# STM32H743IIT6.net
KiCad netlist of a schematic drawn in Altium Designer
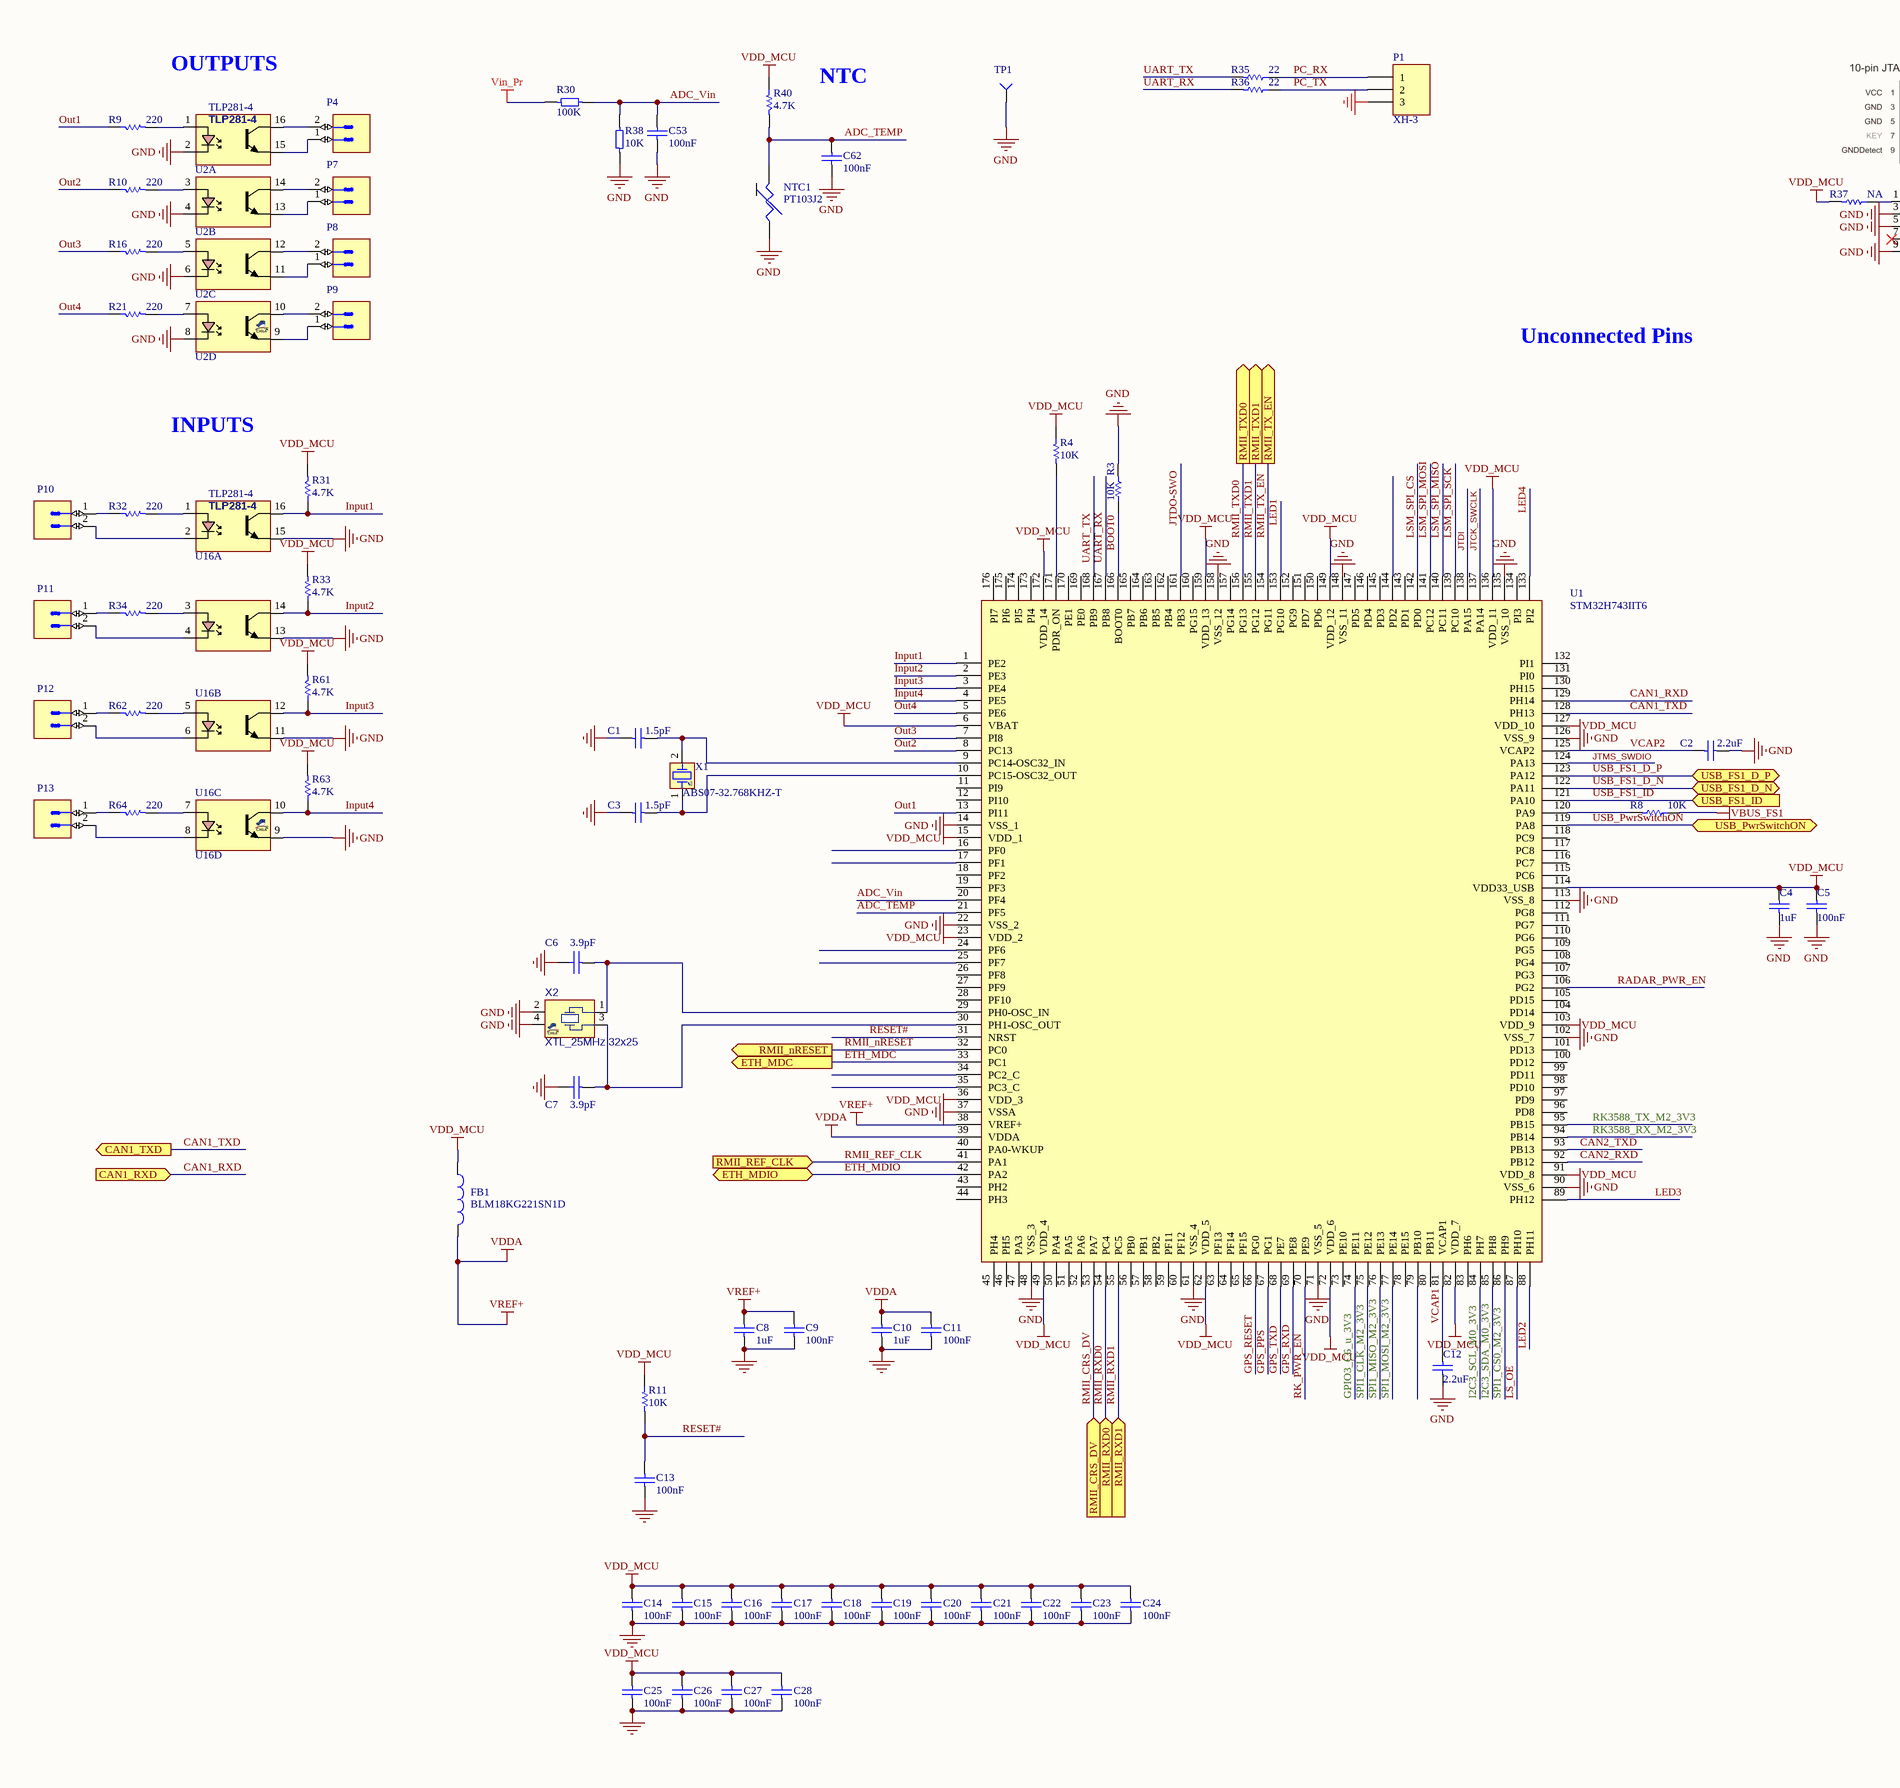
[diagram p0: STM32H743IIT6.SchDoc, left]
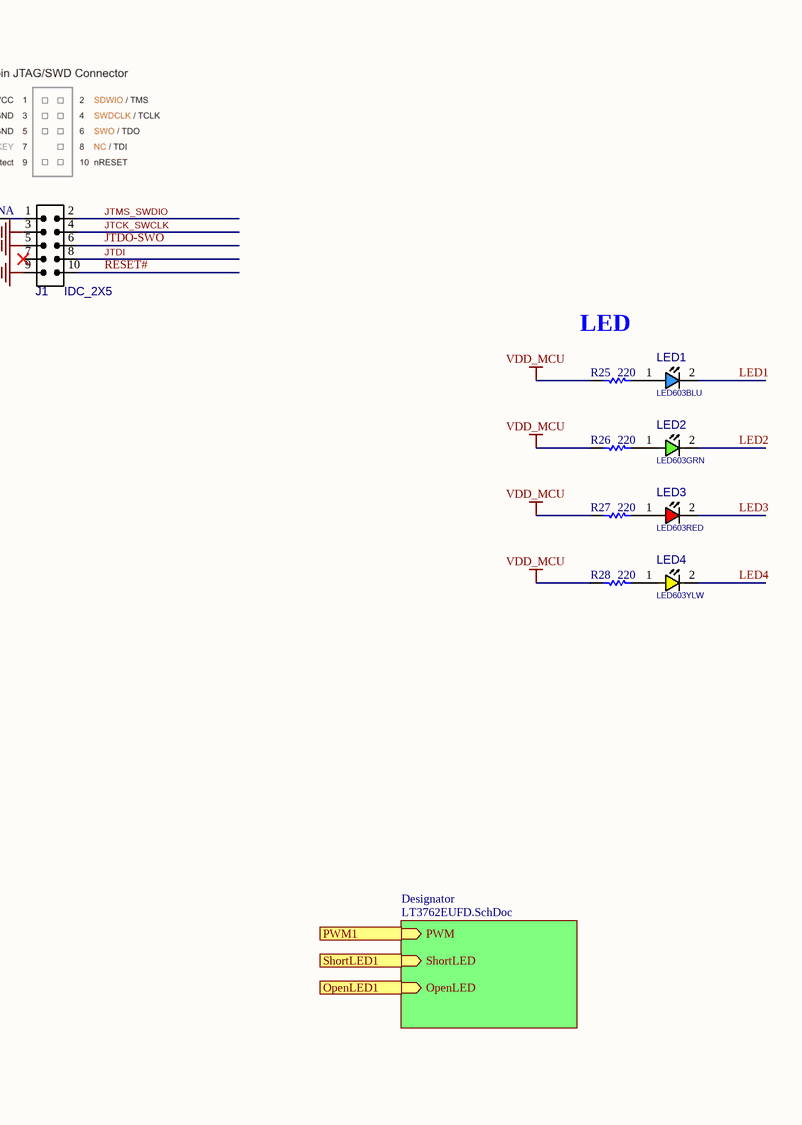
[diagram p1: STM32H743IIT6.SchDoc, right]

(export (version "E")
  (design (tool "Eeschema 10.0.6"))
  (components
    (comp (ref "C1") (value "1.5pF") (footprint "C0603") (libsource (lib "MCD_TOOLS") (part "Capacitor_ST")))
    (comp (ref "C2")
      (value "2.2uF")
      (footprint "C0603")
      (fields (field (name "PUBLISHER") "Altium Limited"))
      (libsource (lib "Miscellaneous Devices") (part "Cap"))
    )
    (comp (ref "C3") (value "1.5pF") (footprint "C0603") (libsource (lib "MCD_TOOLS") (part "Capacitor_ST")))
    (comp (ref "C4")
      (value "1uF")
      (footprint "C0603")
      (fields (field (name "PUBLISHER") "Altium Limited"))
      (libsource (lib "Miscellaneous Devices") (part "Cap"))
    )
    (comp (ref "C5")
      (value "100nF")
      (footprint "C0603")
      (fields (field (name "PUBLISHER") "Altium Limited"))
      (libsource (lib "Miscellaneous Devices") (part "Cap"))
    )
    (comp (ref "C6") (value "3.9pF") (footprint "C0603") (libsource (lib "*") (part "CAP")))
    (comp (ref "C7") (value "3.9pF") (footprint "C0603") (libsource (lib "*") (part "CAP")))
    (comp (ref "C8")
      (value "1uF")
      (footprint "C0603")
      (fields (field (name "PUBLISHER") "Altium Limited"))
      (libsource (lib "Miscellaneous Devices") (part "Cap"))
    )
    (comp (ref "C9")
      (value "100nF")
      (footprint "C0603")
      (fields (field (name "PUBLISHER") "Altium Limited"))
      (libsource (lib "Miscellaneous Devices") (part "Cap"))
    )
    (comp (ref "C10")
      (value "1uF")
      (footprint "C0603")
      (fields (field (name "PUBLISHER") "Altium Limited"))
      (libsource (lib "Miscellaneous Devices") (part "Cap"))
    )
    (comp (ref "C11")
      (value "100nF")
      (footprint "C0603")
      (fields (field (name "PUBLISHER") "Altium Limited"))
      (libsource (lib "Miscellaneous Devices") (part "Cap"))
    )
    (comp (ref "C12")
      (value "2.2uF")
      (footprint "C0603")
      (fields (field (name "PUBLISHER") "Altium Limited"))
      (libsource (lib "Miscellaneous Devices") (part "Cap"))
    )
    (comp (ref "C13")
      (value "100nF")
      (footprint "C0603")
      (fields (field (name "PUBLISHER") "Altium Limited"))
      (libsource (lib "Miscellaneous Devices") (part "CAP"))
    )
    (comp (ref "C14")
      (value "100nF")
      (footprint "C0603")
      (fields (field (name "PUBLISHER") "Altium Limited"))
      (libsource (lib "Miscellaneous Devices") (part "CAP"))
    )
    (comp (ref "C15")
      (value "100nF")
      (footprint "C0603")
      (fields (field (name "PUBLISHER") "Altium Limited"))
      (libsource (lib "Miscellaneous Devices") (part "CAP"))
    )
    (comp (ref "C16")
      (value "100nF")
      (footprint "C0603")
      (fields (field (name "PUBLISHER") "Altium Limited"))
      (libsource (lib "Miscellaneous Devices") (part "CAP"))
    )
    (comp (ref "C17")
      (value "100nF")
      (footprint "C0603")
      (fields (field (name "PUBLISHER") "Altium Limited"))
      (libsource (lib "Miscellaneous Devices") (part "CAP"))
    )
    (comp (ref "C18")
      (value "100nF")
      (footprint "C0603")
      (fields (field (name "PUBLISHER") "Altium Limited"))
      (libsource (lib "Miscellaneous Devices") (part "CAP"))
    )
    (comp (ref "C19")
      (value "100nF")
      (footprint "C0603")
      (fields (field (name "PUBLISHER") "Altium Limited"))
      (libsource (lib "Miscellaneous Devices") (part "CAP"))
    )
    (comp (ref "C20")
      (value "100nF")
      (footprint "C0603")
      (fields (field (name "PUBLISHER") "Altium Limited"))
      (libsource (lib "Miscellaneous Devices") (part "CAP"))
    )
    (comp (ref "C21")
      (value "100nF")
      (footprint "C0603")
      (fields (field (name "PUBLISHER") "Altium Limited"))
      (libsource (lib "Miscellaneous Devices") (part "CAP"))
    )
    (comp (ref "C22")
      (value "100nF")
      (footprint "C0603")
      (fields (field (name "PUBLISHER") "Altium Limited"))
      (libsource (lib "Miscellaneous Devices") (part "CAP"))
    )
    (comp (ref "C23")
      (value "100nF")
      (footprint "C0603")
      (fields (field (name "PUBLISHER") "Altium Limited"))
      (libsource (lib "Miscellaneous Devices") (part "CAP"))
    )
    (comp (ref "C24")
      (value "100nF")
      (footprint "C0603")
      (fields (field (name "PUBLISHER") "Altium Limited"))
      (libsource (lib "Miscellaneous Devices") (part "CAP"))
    )
    (comp (ref "C25")
      (value "100nF")
      (footprint "C0603")
      (fields (field (name "PUBLISHER") "Altium Limited"))
      (libsource (lib "Miscellaneous Devices") (part "CAP"))
    )
    (comp (ref "C26")
      (value "100nF")
      (footprint "C0603")
      (fields (field (name "PUBLISHER") "Altium Limited"))
      (libsource (lib "Miscellaneous Devices") (part "CAP"))
    )
    (comp (ref "C27")
      (value "100nF")
      (footprint "C0603")
      (fields (field (name "PUBLISHER") "Altium Limited"))
      (libsource (lib "Miscellaneous Devices") (part "CAP"))
    )
    (comp (ref "C28")
      (value "100nF")
      (footprint "C0603")
      (fields (field (name "PUBLISHER") "Altium Limited"))
      (libsource (lib "Miscellaneous Devices") (part "CAP"))
    )
    (comp (ref "C53")
      (value "100nF")
      (footprint "C0603")
      (fields (field (name "PUBLISHER") "Altium Limited"))
      (libsource (lib "Miscellaneous Devices") (part "CAP"))
    )
    (comp (ref "C62")
      (value "100nF")
      (footprint "C0603")
      (fields (field (name "PUBLISHER") "Altium Limited"))
      (libsource (lib "Miscellaneous Devices") (part "CAP"))
    )
    (comp (ref "FB1")
      (value "BLM18KG221SN1D")
      (footprint "L0603E")
      (description "Ferrite Bead")
      (fields (field (name "PUBLISHER") "Altium Limited"))
      (libsource (lib "Miscellaneous Devices") (part "Inductor"))
    )
    (comp (ref "J1")
      (value "IDC_2X5")
      (footprint "IDC_2X5")
      (description "CONN, IDC, Male, pitch: 2.54mm, 10POS")
      (libsource (lib "conn_header_idc") (part "IDC_2X5"))
    )
    (comp (ref "LED1")
      (value "LED603BLU")
      (footprint "LED0603BLU")
      (description "LED, SMD, 0603, BLUE")
      (fields (field (name "MANF") "MANF") (field (name "MANF_P#") "MANF_PART#"))
      (libsource (lib "led(diode)") (part "LED_SMD_0603_BLU"))
    )
    (comp (ref "LED2")
      (value "LED603GRN")
      (footprint "LED0603GRN")
      (description "LED, SMD, 0603, GREEN")
      (fields (field (name "MANF") "Kingbright") (field (name "MANF_P#") "APT1608SGC"))
      (libsource (lib "led(diode)") (part "LED_SMD_0603_GRN"))
    )
    (comp (ref "LED3")
      (value "LED603RED")
      (footprint "LED0603RED")
      (description "LED, SMD, 0603, RED")
      (fields (field (name "MANF") "MANF") (field (name "MANF_P#") "MANF_PART#"))
      (libsource (lib "led(diode)") (part "LED_SMD_0603_RED"))
    )
    (comp (ref "LED4")
      (value "LED603YLW")
      (footprint "LED0603YLW")
      (description "LED, SMD, 0603, YELLOW")
      (fields (field (name "MANF") "MANF") (field (name "MANF_P#") "MANF_PART#"))
      (libsource (lib "led(diode)") (part "LED_SMD_0603_YLW"))
    )
    (comp (ref "NTC1")
      (value "PT103J2")
      (footprint "HDR1X2")
      (description "THERMISTOR 10K OHM +/-0.20 C")
      (libsource (lib "J ABDAR-Altium-LibV1") (part "NTC power"))
    )
    (comp (ref "P1")
      (value "XH-3")
      (footprint "xh-3")
      (description "Header, 3-Pin")
      (fields (field (name "PUBLISHER") "Altium Limited"))
      (libsource (lib "Miscellaneous Connectors") (part "Header 3"))
    )
    (comp (ref "P4")
      (value "JST PH 2mm 2P RIGHT")
      (footprint "JST B2B-PH-K")
      (description "JST PH 2P RIGHT")
      (fields
        (field (name "PART NUMBER") "PHOENIX_1803426")
        (field (name "MANUFACTURER") "PHOENIX CONTACT")
        (field (name "AUTHOR") "CERN DEM JLC")
      )
      (libsource (lib "") (part "Connector 2 Male_1"))
    )
    (comp (ref "P7")
      (value "JST PH 2mm 2P RIGHT")
      (footprint "JST B2B-PH-K")
      (description "JST PH 2P RIGHT")
      (fields
        (field (name "PART NUMBER") "PHOENIX_1803426")
        (field (name "MANUFACTURER") "PHOENIX CONTACT")
        (field (name "AUTHOR") "CERN DEM JLC")
      )
      (libsource (lib "") (part "Connector 2 Male_1"))
    )
    (comp (ref "P8")
      (value "JST PH 2mm 2P RIGHT")
      (footprint "JST B2B-PH-K")
      (description "JST PH 2P RIGHT")
      (fields
        (field (name "PART NUMBER") "PHOENIX_1803426")
        (field (name "MANUFACTURER") "PHOENIX CONTACT")
        (field (name "AUTHOR") "CERN DEM JLC")
      )
      (libsource (lib "") (part "Connector 2 Male_1"))
    )
    (comp (ref "P9")
      (value "JST PH 2mm 2P RIGHT")
      (footprint "JST B2B-PH-K")
      (description "JST PH 2P RIGHT")
      (fields
        (field (name "PART NUMBER") "PHOENIX_1803426")
        (field (name "MANUFACTURER") "PHOENIX CONTACT")
        (field (name "AUTHOR") "CERN DEM JLC")
      )
      (libsource (lib "") (part "Connector 2 Male_1"))
    )
    (comp (ref "P10")
      (value "JST PH 2mm 2P RIGHT")
      (footprint "JST B2B-PH-K")
      (description "JST PH 2P RIGHT")
      (fields
        (field (name "PART NUMBER") "PHOENIX_1803426")
        (field (name "MANUFACTURER") "PHOENIX CONTACT")
        (field (name "AUTHOR") "CERN DEM JLC")
      )
      (libsource (lib "Connectors") (part "Connector 2 Male"))
    )
    (comp (ref "P11")
      (value "JST PH 2mm 2P RIGHT")
      (footprint "JST B2B-PH-K")
      (description "JST PH 2P RIGHT")
      (fields
        (field (name "PART NUMBER") "PHOENIX_1803426")
        (field (name "MANUFACTURER") "PHOENIX CONTACT")
        (field (name "AUTHOR") "CERN DEM JLC")
      )
      (libsource (lib "Connectors") (part "Connector 2 Male"))
    )
    (comp (ref "P12")
      (value "JST PH 2mm 2P RIGHT")
      (footprint "JST B2B-PH-K")
      (description "JST PH 2P RIGHT")
      (fields
        (field (name "PART NUMBER") "PHOENIX_1803426")
        (field (name "MANUFACTURER") "PHOENIX CONTACT")
        (field (name "AUTHOR") "CERN DEM JLC")
      )
      (libsource (lib "Connectors") (part "Connector 2 Male"))
    )
    (comp (ref "P13")
      (value "JST PH 2mm 2P RIGHT")
      (footprint "JST B2B-PH-K")
      (description "JST PH 2P RIGHT")
      (fields
        (field (name "PART NUMBER") "PHOENIX_1803426")
        (field (name "MANUFACTURER") "PHOENIX CONTACT")
        (field (name "AUTHOR") "CERN DEM JLC")
      )
      (libsource (lib "Connectors") (part "Connector 2 Male"))
    )
    (comp (ref "R3")
      (value "10K")
      (footprint "R0603")
      (fields (field (name "PUBLISHER") "Altium Limited"))
      (libsource (lib "Miscellaneous Devices") (part "res1"))
    )
    (comp (ref "R4")
      (value "10K")
      (footprint "R0603")
      (fields (field (name "PUBLISHER") "Altium Limited"))
      (libsource (lib "Miscellaneous Devices") (part "Res1"))
    )
    (comp (ref "R8")
      (value "10K")
      (footprint "R0603")
      (fields (field (name "PUBLISHER") "Altium Limited"))
      (libsource (lib "Miscellaneous Devices") (part "Res1"))
    )
    (comp (ref "R9")
      (value "220")
      (footprint "R0603")
      (fields (field (name "PUBLISHER") "Altium Limited"))
      (libsource (lib "Miscellaneous Devices") (part "Res1"))
    )
    (comp (ref "R10")
      (value "220")
      (footprint "R0603")
      (fields (field (name "PUBLISHER") "Altium Limited"))
      (libsource (lib "Miscellaneous Devices") (part "Res1"))
    )
    (comp (ref "R11")
      (value "10K")
      (footprint "R0603")
      (fields (field (name "PUBLISHER") "Altium Limited"))
      (libsource (lib "Miscellaneous Devices") (part "Res1"))
    )
    (comp (ref "R16")
      (value "220")
      (footprint "R0603")
      (fields (field (name "PUBLISHER") "Altium Limited"))
      (libsource (lib "Miscellaneous Devices") (part "Res1"))
    )
    (comp (ref "R21")
      (value "220")
      (footprint "R0603")
      (fields (field (name "PUBLISHER") "Altium Limited"))
      (libsource (lib "Miscellaneous Devices") (part "Res1"))
    )
    (comp (ref "R25")
      (value "220")
      (footprint "R0603")
      (fields (field (name "PUBLISHER") "Altium Limited"))
      (libsource (lib "Miscellaneous Devices") (part "Res1"))
    )
    (comp (ref "R26")
      (value "220")
      (footprint "R0603")
      (fields (field (name "PUBLISHER") "Altium Limited"))
      (libsource (lib "Miscellaneous Devices") (part "Res1"))
    )
    (comp (ref "R27")
      (value "220")
      (footprint "R0603")
      (fields (field (name "PUBLISHER") "Altium Limited"))
      (libsource (lib "Miscellaneous Devices") (part "Res1"))
    )
    (comp (ref "R28")
      (value "220")
      (footprint "R0603")
      (fields (field (name "PUBLISHER") "Altium Limited"))
      (libsource (lib "Miscellaneous Devices") (part "Res1"))
    )
    (comp (ref "R30")
      (value "100K")
      (footprint "R0603")
      (libsource (lib "Rahimi librery") (part "Resistor SMD"))
    )
    (comp (ref "R31")
      (value "4.7K")
      (footprint "R0603")
      (fields (field (name "PUBLISHER") "Altium Limited"))
      (libsource (lib "Miscellaneous Devices") (part "Res1"))
    )
    (comp (ref "R32")
      (value "220")
      (footprint "R0603")
      (fields (field (name "PUBLISHER") "Altium Limited"))
      (libsource (lib "Miscellaneous Devices") (part "Res1"))
    )
    (comp (ref "R33")
      (value "4.7K")
      (footprint "R0603")
      (fields (field (name "PUBLISHER") "Altium Limited"))
      (libsource (lib "Miscellaneous Devices") (part "Res1"))
    )
    (comp (ref "R34")
      (value "220")
      (footprint "R0603")
      (fields (field (name "PUBLISHER") "Altium Limited"))
      (libsource (lib "Miscellaneous Devices") (part "Res1"))
    )
    (comp (ref "R35")
      (value "22")
      (footprint "R0603")
      (fields (field (name "PUBLISHER") "Altium Limited"))
      (libsource (lib "Miscellaneous Devices") (part "res1"))
    )
    (comp (ref "R36")
      (value "22")
      (footprint "R0603")
      (fields (field (name "PUBLISHER") "Altium Limited"))
      (libsource (lib "Miscellaneous Devices") (part "res1"))
    )
    (comp (ref "R37")
      (value "NA")
      (footprint "R0603")
      (fields (field (name "PUBLISHER") "Altium Limited"))
      (libsource (lib "Miscellaneous Devices") (part "Res1"))
    )
    (comp (ref "R38")
      (value "10K")
      (footprint "R0603")
      (libsource (lib "Rahimi librery") (part "Resistor SMD"))
    )
    (comp (ref "R40")
      (value "4.7K")
      (footprint "R0603")
      (fields (field (name "PUBLISHER") "Altium Limited"))
      (libsource (lib "Miscellaneous Devices") (part "Res1"))
    )
    (comp (ref "R61")
      (value "4.7K")
      (footprint "R0603")
      (fields (field (name "PUBLISHER") "Altium Limited"))
      (libsource (lib "Miscellaneous Devices") (part "Res1"))
    )
    (comp (ref "R62")
      (value "220")
      (footprint "R0603")
      (fields (field (name "PUBLISHER") "Altium Limited"))
      (libsource (lib "Miscellaneous Devices") (part "Res1"))
    )
    (comp (ref "R63")
      (value "4.7K")
      (footprint "R0603")
      (fields (field (name "PUBLISHER") "Altium Limited"))
      (libsource (lib "Miscellaneous Devices") (part "Res1"))
    )
    (comp (ref "R64")
      (value "220")
      (footprint "R0603")
      (fields (field (name "PUBLISHER") "Altium Limited"))
      (libsource (lib "Miscellaneous Devices") (part "Res1"))
    )
    (comp (ref "TP1")
      (value "TEST POINT")
      (footprint "TEST_POINT")
      (libsource (lib "Tracker_MAIN_V1.01") (part "TEST POINT"))
    )
    (comp (ref "U1")
      (value "STM32H743IIT6")
      (footprint "QFP50P2600X2600X160-176N")
      (description "Integrated Circuit")
      (fields (field (name "MOUSER PART NUMBER") "511-STM32H743IIT6"))
      (libsource (lib "*") (part "STM32H743IIT6"))
    )
    (comp (ref "U2")
      (value "TLP281-4")
      (footprint "SO_16")
      (description "OPTOCOUPLER, TRANSISTOR, QUAD")
      (fields (field (name "MANF_P#") "TLP281-4A"))
      (libsource (lib "optocoupler") (part "OPTC_TR16P_TLP281-4_SMD"))
    )
    (comp (ref "U16")
      (value "TLP281-4")
      (footprint "SO_16")
      (description "OPTOCOUPLER, TRANSISTOR, QUAD")
      (fields (field (name "MANF_P#") "TLP281-4A"))
      (libsource (lib "optocoupler") (part "OPTC_TR16P_TLP281-4_SMD"))
    )
    (comp (ref "X1")
      (value "ABS07-32.768KHZ-T")
      (footprint "XTL_2_3215")
      (description "Crystal, 32.768KHz, 3pF, 20PPM")
      (fields (field (name "MANF") "ABRACON") (field (name "MANF_P#") "ABS07W-32.768kHz-D-2-T"))
      (libsource (lib "crystal") (part "XTL_2_32.768_3215A"))
    )
    (comp (ref "X2")
      (value "XTL_25MHz 32x25")
      (footprint "XTL_4_3225")
      (description "CRYSTAL 25.00 MHZ 18pF, 10PPM")
      (fields (field (name "MANF") "EPSON") (field (name "MANF_P#") "TSX-3225 25.0000MF10P-C3"))
      (libsource (lib "crystal") (part "XTL_4_25MHz_3225"))
    )
  )
  (nets
    (net (code "1") (name "/ADC_TEMP") (class "Default")
      (node (ref "C62") (pin "2") (pinfunction "2_2") (pintype "passive"))
      (node (ref "NTC1") (pin "2") (pintype "passive"))
      (node (ref "R40") (pin "2") (pinfunction "2_2") (pintype "passive"))
      (node (ref "U1") (pin "21") (pinfunction "PF5_21") (pintype "passive"))
    )
    (net (code "2") (name "/ADC_Vin") (class "Default")
      (node (ref "C53") (pin "2") (pinfunction "2_2") (pintype "passive"))
      (node (ref "R30") (pin "2") (pintype "passive"))
      (node (ref "R38") (pin "2") (pintype "passive"))
      (node (ref "U1") (pin "20") (pinfunction "PF4_20") (pintype "passive"))
    )
    (net (code "3") (name "/BOOT0") (class "Default")
      (node (ref "R3") (pin "1") (pinfunction "1_1") (pintype "passive"))
      (node (ref "U1") (pin "166") (pinfunction "BOOT0_166") (pintype "passive"))
    )
    (net (code "4") (name "/CAN1_RXD") (class "Default")
      (node (ref "U1") (pin "129") (pinfunction "PH14_129") (pintype "passive"))
    )
    (net (code "5") (name "/CAN1_TXD") (class "Default")
      (node (ref "U1") (pin "128") (pinfunction "PH13_128") (pintype "passive"))
    )
    (net (code "6") (name "/CAN2_RXD") (class "Default")
      (node (ref "U1") (pin "92") (pinfunction "PB12_92") (pintype "passive"))
    )
    (net (code "7") (name "/CAN2_TXD") (class "Default")
      (node (ref "U1") (pin "93") (pinfunction "PB13_93") (pintype "passive"))
    )
    (net (code "8") (name "/ETH_MDC") (class "Default")
      (node (ref "U1") (pin "33") (pinfunction "PC1_33") (pintype "passive"))
    )
    (net (code "9") (name "/ETH_MDIO") (class "Default")
      (node (ref "U1") (pin "42") (pinfunction "PA2_42") (pintype "passive"))
    )
    (net (code "10") (name "/GPIO3_C6_u_3V3") (class "Default")
      (node (ref "U1") (pin "74") (pinfunction "PE11_74") (pintype "passive"))
    )
    (net (code "11") (name "/GPS_PPS") (class "Default")
      (node (ref "U1") (pin "67") (pinfunction "PG1_67") (pintype "passive"))
    )
    (net (code "12") (name "/GPS_RESET") (class "Default")
      (node (ref "U1") (pin "66") (pinfunction "PG0_66") (pintype "passive"))
    )
    (net (code "13") (name "/GPS_RXD") (class "Default")
      (node (ref "U1") (pin "69") (pinfunction "PE8_69") (pintype "passive"))
    )
    (net (code "14") (name "/GPS_TXD") (class "Default")
      (node (ref "U1") (pin "68") (pinfunction "PE7_68") (pintype "passive"))
    )
    (net (code "15") (name "/I2C3_SCL_M0_3V3") (class "Default")
      (node (ref "U1") (pin "84") (pinfunction "PH7_84") (pintype "passive"))
    )
    (net (code "16") (name "/I2C3_SDA_M0_3V3") (class "Default")
      (node (ref "U1") (pin "85") (pinfunction "PH8_85") (pintype "passive"))
    )
    (net (code "17") (name "/Input1") (class "Default")
      (node (ref "R31") (pin "1") (pinfunction "1_1") (pintype "passive"))
      (node (ref "U1") (pin "1") (pinfunction "PE2_1") (pintype "passive"))
      (node (ref "U16") (pin "16") (pinfunction "16_16") (pintype "power_in"))
    )
    (net (code "18") (name "/Input2") (class "Default")
      (node (ref "R33") (pin "1") (pinfunction "1_1") (pintype "passive"))
      (node (ref "U1") (pin "2") (pinfunction "PE3_2") (pintype "passive"))
      (node (ref "U16") (pin "14") (pinfunction "14_14") (pintype "power_in"))
    )
    (net (code "19") (name "/Input3") (class "Default")
      (node (ref "R61") (pin "1") (pinfunction "1_1") (pintype "passive"))
      (node (ref "U1") (pin "3") (pinfunction "PE4_3") (pintype "passive"))
      (node (ref "U16") (pin "12") (pinfunction "12_12") (pintype "power_in"))
    )
    (net (code "20") (name "/Input4") (class "Default")
      (node (ref "R63") (pin "1") (pinfunction "1_1") (pintype "passive"))
      (node (ref "U1") (pin "4") (pinfunction "PE5_4") (pintype "passive"))
      (node (ref "U16") (pin "10") (pinfunction "10_10") (pintype "power_in"))
    )
    (net (code "21") (name "/JTCK_SWCLK") (class "Default")
      (node (ref "J1") (pin "4") (pinfunction "4_4") (pintype "passive"))
      (node (ref "U1") (pin "137") (pinfunction "PA14_137") (pintype "passive"))
    )
    (net (code "22") (name "/JTDI") (class "Default")
      (node (ref "J1") (pin "8") (pinfunction "8_8") (pintype "passive"))
      (node (ref "U1") (pin "138") (pinfunction "PA15_138") (pintype "passive"))
    )
    (net (code "23") (name "/JTDO-SWO") (class "Default")
      (node (ref "J1") (pin "6") (pinfunction "6_6") (pintype "passive"))
      (node (ref "U1") (pin "161") (pinfunction "PB3_161") (pintype "passive"))
    )
    (net (code "24") (name "/JTMS_SWDIO") (class "Default")
      (node (ref "J1") (pin "2") (pinfunction "2_2") (pintype "passive"))
      (node (ref "U1") (pin "124") (pinfunction "PA13_124") (pintype "passive"))
    )
    (net (code "25") (name "/LED1") (class "Default")
      (node (ref "LED1") (pin "2") (pinfunction "CATHODE_2") (pintype "passive"))
      (node (ref "U1") (pin "153") (pinfunction "PG10_153") (pintype "passive"))
    )
    (net (code "26") (name "/LED2") (class "Default")
      (node (ref "LED2") (pin "2") (pinfunction "CATHODE_2") (pintype "passive"))
      (node (ref "U1") (pin "88") (pinfunction "PH11_88") (pintype "passive"))
    )
    (net (code "27") (name "/LED3") (class "Default")
      (node (ref "LED3") (pin "2") (pinfunction "CATHODE_2") (pintype "passive"))
      (node (ref "U1") (pin "89") (pinfunction "PH12_89") (pintype "passive"))
    )
    (net (code "28") (name "/LED4") (class "Default")
      (node (ref "LED4") (pin "2") (pinfunction "CATHODE_2") (pintype "passive"))
      (node (ref "U1") (pin "133") (pinfunction "PI2_133") (pintype "passive"))
    )
    (net (code "29") (name "/LSM_SPI_CS") (class "Default")
      (node (ref "U1") (pin "142") (pinfunction "PD0_142") (pintype "passive"))
    )
    (net (code "30") (name "/LSM_SPI_MISO") (class "Default")
      (node (ref "U1") (pin "140") (pinfunction "PC11_140") (pintype "passive"))
    )
    (net (code "31") (name "/LSM_SPI_MOSI") (class "Default")
      (node (ref "U1") (pin "141") (pinfunction "PC12_141") (pintype "passive"))
    )
    (net (code "32") (name "/LSM_SPI_SCK") (class "Default")
      (node (ref "U1") (pin "139") (pinfunction "PC10_139") (pintype "passive"))
    )
    (net (code "33") (name "/LS_OE") (class "Default")
      (node (ref "U1") (pin "87") (pinfunction "PH10_87") (pintype "passive"))
    )
    (net (code "35") (name "/Out1") (class "Default")
      (node (ref "R9") (pin "1") (pinfunction "1_1") (pintype "passive"))
      (node (ref "U1") (pin "13") (pinfunction "PI11_13") (pintype "passive"))
    )
    (net (code "36") (name "/Out2") (class "Default")
      (node (ref "R10") (pin "1") (pinfunction "1_1") (pintype "passive"))
      (node (ref "U1") (pin "8") (pinfunction "PC13_8") (pintype "passive"))
    )
    (net (code "37") (name "/Out3") (class "Default")
      (node (ref "R16") (pin "1") (pinfunction "1_1") (pintype "passive"))
      (node (ref "U1") (pin "7") (pinfunction "PI8_7") (pintype "passive"))
    )
    (net (code "38") (name "/Out4") (class "Default")
      (node (ref "R21") (pin "1") (pinfunction "1_1") (pintype "passive"))
      (node (ref "U1") (pin "5") (pinfunction "PE6_5") (pintype "passive"))
    )
    (net (code "39") (name "/PC_RX") (class "Default")
      (node (ref "P1") (pin "1") (pinfunction "1_1") (pintype "passive"))
      (node (ref "R35") (pin "1") (pinfunction "1_1") (pintype "passive"))
    )
    (net (code "40") (name "/PC_TX") (class "Default")
      (node (ref "P1") (pin "2") (pinfunction "2_2") (pintype "passive"))
      (node (ref "R36") (pin "1") (pinfunction "1_1") (pintype "passive"))
    )
    (net (code "42") (name "/RADAR_PWR_EN") (class "Default")
      (node (ref "U1") (pin "106") (pinfunction "PG2_106") (pintype "passive"))
    )
    (net (code "43") (name "/RESET#") (class "Default")
      (node (ref "C13") (pin "2") (pinfunction "2_2") (pintype "passive"))
      (node (ref "J1") (pin "10") (pinfunction "10_10") (pintype "passive"))
      (node (ref "R11") (pin "2") (pinfunction "2_2") (pintype "passive"))
      (node (ref "U1") (pin "31") (pinfunction "NRST_31") (pintype "passive"))
    )
    (net (code "44") (name "/RK3588_RX_M2_3V3") (class "Default")
      (node (ref "U1") (pin "94") (pinfunction "PB14_94") (pintype "passive"))
    )
    (net (code "45") (name "/RK3588_TX_M2_3V3") (class "Default")
      (node (ref "U1") (pin "95") (pinfunction "PB15_95") (pintype "passive"))
    )
    (net (code "46") (name "/RK_PWR_EN") (class "Default")
      (node (ref "U1") (pin "70") (pinfunction "PE9_70") (pintype "passive"))
    )
    (net (code "47") (name "/RMII_CRS_DV") (class "Default")
      (node (ref "U1") (pin "53") (pinfunction "PA7_53") (pintype "passive"))
    )
    (net (code "48") (name "/RMII_REF_CLK") (class "Default")
      (node (ref "U1") (pin "41") (pinfunction "PA1_41") (pintype "passive"))
    )
    (net (code "49") (name "/RMII_RXD0") (class "Default")
      (node (ref "U1") (pin "54") (pinfunction "PC4_54") (pintype "passive"))
    )
    (net (code "50") (name "/RMII_RXD1") (class "Default")
      (node (ref "U1") (pin "55") (pinfunction "PC5_55") (pintype "passive"))
    )
    (net (code "51") (name "/RMII_TXD0") (class "Default")
      (node (ref "U1") (pin "156") (pinfunction "PG13_156") (pintype "passive"))
    )
    (net (code "52") (name "/RMII_TXD1") (class "Default")
      (node (ref "U1") (pin "155") (pinfunction "PG12_155") (pintype "passive"))
    )
    (net (code "53") (name "/RMII_TX_EN") (class "Default")
      (node (ref "U1") (pin "154") (pinfunction "PG11_154") (pintype "passive"))
    )
    (net (code "54") (name "/RMII_nRESET") (class "Default")
      (node (ref "U1") (pin "32") (pinfunction "PC0_32") (pintype "passive"))
    )
    (net (code "55") (name "/SPI1_CLK_M2_3V3") (class "Default")
      (node (ref "U1") (pin "75") (pinfunction "PE12_75") (pintype "passive"))
    )
    (net (code "56") (name "/SPI1_CS0_M2_3V3") (class "Default")
      (node (ref "U1") (pin "86") (pinfunction "PH9_86") (pintype "passive"))
    )
    (net (code "57") (name "/SPI1_MISO_M2_3V3") (class "Default")
      (node (ref "U1") (pin "76") (pinfunction "PE13_76") (pintype "passive"))
    )
    (net (code "58") (name "/SPI1_MOSI_M2_3V3") (class "Default")
      (node (ref "U1") (pin "77") (pinfunction "PE14_77") (pintype "passive"))
    )
    (net (code "60") (name "/UART_RX") (class "Default")
      (node (ref "R36") (pin "2") (pinfunction "2_2") (pintype "passive"))
      (node (ref "U1") (pin "167") (pinfunction "PB8_167") (pintype "passive"))
    )
    (net (code "61") (name "/UART_TX") (class "Default")
      (node (ref "R35") (pin "2") (pinfunction "2_2") (pintype "passive"))
      (node (ref "U1") (pin "168") (pinfunction "PB9_168") (pintype "passive"))
    )
    (net (code "62") (name "/USB_FS1_D_N") (class "Default")
      (node (ref "U1") (pin "122") (pinfunction "PA11_122") (pintype "passive"))
    )
    (net (code "63") (name "/USB_FS1_D_P") (class "Default")
      (node (ref "U1") (pin "123") (pinfunction "PA12_123") (pintype "passive"))
    )
    (net (code "64") (name "/USB_FS1_ID") (class "Default")
      (node (ref "U1") (pin "121") (pinfunction "PA10_121") (pintype "passive"))
    )
    (net (code "65") (name "/USB_PwrSwitchON") (class "Default")
      (node (ref "U1") (pin "119") (pinfunction "PA8_119") (pintype "passive"))
    )
    (net (code "66") (name "/VCAP1") (class "Default")
      (node (ref "C12") (pin "2") (pinfunction "2_2") (pintype "passive"))
      (node (ref "U1") (pin "81") (pinfunction "VCAP1_81") (pintype "power_in"))
    )
    (net (code "67") (name "/VCAP2") (class "Default")
      (node (ref "C2") (pin "1") (pinfunction "1_1") (pintype "passive"))
      (node (ref "U1") (pin "125") (pinfunction "VCAP2_125") (pintype "power_in"))
    )
    (net (code "68") (name "GND") (class "Default")
      (node (ref "C1") (pin "2") (pinfunction "2_2") (pintype "passive"))
      (node (ref "C10") (pin "1") (pinfunction "1_1") (pintype "passive"))
      (node (ref "C11") (pin "1") (pinfunction "1_1") (pintype "passive"))
      (node (ref "C12") (pin "1") (pinfunction "1_1") (pintype "passive"))
      (node (ref "C13") (pin "1") (pinfunction "1_1") (pintype "passive"))
      (node (ref "C14") (pin "2") (pinfunction "2_2") (pintype "passive"))
      (node (ref "C15") (pin "2") (pinfunction "2_2") (pintype "passive"))
      (node (ref "C16") (pin "2") (pinfunction "2_2") (pintype "passive"))
      (node (ref "C17") (pin "2") (pinfunction "2_2") (pintype "passive"))
      (node (ref "C18") (pin "2") (pinfunction "2_2") (pintype "passive"))
      (node (ref "C19") (pin "2") (pinfunction "2_2") (pintype "passive"))
      (node (ref "C2") (pin "2") (pinfunction "2_2") (pintype "passive"))
      (node (ref "C20") (pin "2") (pinfunction "2_2") (pintype "passive"))
      (node (ref "C21") (pin "2") (pinfunction "2_2") (pintype "passive"))
      (node (ref "C22") (pin "2") (pinfunction "2_2") (pintype "passive"))
      (node (ref "C23") (pin "2") (pinfunction "2_2") (pintype "passive"))
      (node (ref "C24") (pin "2") (pinfunction "2_2") (pintype "passive"))
      (node (ref "C25") (pin "2") (pinfunction "2_2") (pintype "passive"))
      (node (ref "C26") (pin "2") (pinfunction "2_2") (pintype "passive"))
      (node (ref "C27") (pin "2") (pinfunction "2_2") (pintype "passive"))
      (node (ref "C28") (pin "2") (pinfunction "2_2") (pintype "passive"))
      (node (ref "C3") (pin "2") (pinfunction "2_2") (pintype "passive"))
      (node (ref "C4") (pin "1") (pinfunction "1_1") (pintype "passive"))
      (node (ref "C5") (pin "1") (pinfunction "1_1") (pintype "passive"))
      (node (ref "C53") (pin "1") (pinfunction "1_1") (pintype "passive"))
      (node (ref "C6") (pin "2") (pinfunction "2_2") (pintype "passive"))
      (node (ref "C62") (pin "1") (pinfunction "1_1") (pintype "passive"))
      (node (ref "C7") (pin "2") (pinfunction "2_2") (pintype "passive"))
      (node (ref "C8") (pin "1") (pinfunction "1_1") (pintype "passive"))
      (node (ref "C9") (pin "1") (pinfunction "1_1") (pintype "passive"))
      (node (ref "J1") (pin "3") (pinfunction "3_3") (pintype "passive"))
      (node (ref "J1") (pin "5") (pinfunction "5_5") (pintype "passive"))
      (node (ref "J1") (pin "9") (pinfunction "9_9") (pintype "passive"))
      (node (ref "NTC1") (pin "1") (pintype "passive"))
      (node (ref "P1") (pin "3") (pinfunction "3_3") (pintype "passive"))
      (node (ref "R3") (pin "2") (pinfunction "2_2") (pintype "passive"))
      (node (ref "R38") (pin "1") (pintype "passive"))
      (node (ref "TP1") (pin "1") (pinfunction "TP_1") (pintype "passive"))
      (node (ref "U1") (pin "102") (pinfunction "VSS_7_102") (pintype "power_in"))
      (node (ref "U1") (pin "113") (pinfunction "VSS_8_113") (pintype "power_in"))
      (node (ref "U1") (pin "126") (pinfunction "VSS_9_126") (pintype "power_in"))
      (node (ref "U1") (pin "135") (pinfunction "VSS_10_135") (pintype "power_in"))
      (node (ref "U1") (pin "14") (pinfunction "VSS_1_14") (pintype "power_in"))
      (node (ref "U1") (pin "148") (pinfunction "VSS_11_148") (pintype "power_in"))
      (node (ref "U1") (pin "158") (pinfunction "VSS_12_158") (pintype "power_in"))
      (node (ref "U1") (pin "22") (pinfunction "VSS_2_22") (pintype "power_in"))
      (node (ref "U1") (pin "37") (pinfunction "VSSA_37") (pintype "power_in"))
      (node (ref "U1") (pin "48") (pinfunction "VSS_3_48") (pintype "power_in"))
      (node (ref "U1") (pin "61") (pinfunction "VSS_4_61") (pintype "power_in"))
      (node (ref "U1") (pin "71") (pinfunction "VSS_5_71") (pintype "power_in"))
      (node (ref "U1") (pin "90") (pinfunction "VSS_6_90") (pintype "power_in"))
      (node (ref "U16") (pin "11") (pinfunction "11_11") (pintype "power_in"))
      (node (ref "U16") (pin "13") (pinfunction "13_13") (pintype "power_in"))
      (node (ref "U16") (pin "15") (pinfunction "15_15") (pintype "power_in"))
      (node (ref "U16") (pin "9") (pinfunction "9_9") (pintype "power_in"))
      (node (ref "U2") (pin "2") (pinfunction "2_2") (pintype "passive"))
      (node (ref "U2") (pin "4") (pinfunction "4_4") (pintype "power_in"))
      (node (ref "U2") (pin "6") (pinfunction "6_6") (pintype "power_in"))
      (node (ref "U2") (pin "8") (pinfunction "8_8") (pintype "power_in"))
      (node (ref "X2") (pin "2") (pinfunction "2_2") (pintype "passive"))
      (node (ref "X2") (pin "4") (pinfunction "4_4") (pintype "passive"))
    )
    (net (code "69") (name "Net-(J1-Pad1)") (class "Default")
      (node (ref "J1") (pin "1") (pinfunction "1_1") (pintype "passive"))
      (node (ref "R37") (pin "1") (pinfunction "1_1") (pintype "passive"))
    )
    (net (code "70") (name "Net-(LED1-ANODE)") (class "Default")
      (node (ref "LED1") (pin "1") (pinfunction "ANODE_1") (pintype "passive"))
      (node (ref "R25") (pin "2") (pinfunction "2_2") (pintype "passive"))
    )
    (net (code "71") (name "Net-(LED2-ANODE)") (class "Default")
      (node (ref "LED2") (pin "1") (pinfunction "ANODE_1") (pintype "passive"))
      (node (ref "R26") (pin "2") (pinfunction "2_2") (pintype "passive"))
    )
    (net (code "72") (name "Net-(LED3-ANODE)") (class "Default")
      (node (ref "LED3") (pin "1") (pinfunction "ANODE_1") (pintype "passive"))
      (node (ref "R27") (pin "2") (pinfunction "2_2") (pintype "passive"))
    )
    (net (code "73") (name "Net-(LED4-ANODE)") (class "Default")
      (node (ref "LED4") (pin "1") (pinfunction "ANODE_1") (pintype "passive"))
      (node (ref "R28") (pin "2") (pinfunction "2_2") (pintype "passive"))
    )
    (net (code "74") (name "Net-(P4-Pad1)") (class "Default")
      (node (ref "P4") (pin "1") (pinfunction "1_1") (pintype "bidirectional"))
      (node (ref "U2") (pin "15") (pinfunction "15_15") (pintype "power_in"))
    )
    (net (code "75") (name "Net-(P4-Pad2)") (class "Default")
      (node (ref "P4") (pin "2") (pinfunction "2_2") (pintype "bidirectional"))
      (node (ref "U2") (pin "16") (pinfunction "16_16") (pintype "power_in"))
    )
    (net (code "76") (name "Net-(P7-Pad1)") (class "Default")
      (node (ref "P7") (pin "1") (pinfunction "1_1") (pintype "bidirectional"))
      (node (ref "U2") (pin "13") (pinfunction "13_13") (pintype "power_in"))
    )
    (net (code "77") (name "Net-(P7-Pad2)") (class "Default")
      (node (ref "P7") (pin "2") (pinfunction "2_2") (pintype "bidirectional"))
      (node (ref "U2") (pin "14") (pinfunction "14_14") (pintype "power_in"))
    )
    (net (code "78") (name "Net-(P8-Pad1)") (class "Default")
      (node (ref "P8") (pin "1") (pinfunction "1_1") (pintype "bidirectional"))
      (node (ref "U2") (pin "11") (pinfunction "11_11") (pintype "power_in"))
    )
    (net (code "79") (name "Net-(P8-Pad2)") (class "Default")
      (node (ref "P8") (pin "2") (pinfunction "2_2") (pintype "bidirectional"))
      (node (ref "U2") (pin "12") (pinfunction "12_12") (pintype "power_in"))
    )
    (net (code "80") (name "Net-(P9-Pad1)") (class "Default")
      (node (ref "P9") (pin "1") (pinfunction "1_1") (pintype "bidirectional"))
      (node (ref "U2") (pin "9") (pinfunction "9_9") (pintype "power_in"))
    )
    (net (code "81") (name "Net-(P9-Pad2)") (class "Default")
      (node (ref "P9") (pin "2") (pinfunction "2_2") (pintype "bidirectional"))
      (node (ref "U2") (pin "10") (pinfunction "10_10") (pintype "power_in"))
    )
    (net (code "82") (name "Net-(P10-Pad1)") (class "Default")
      (node (ref "P10") (pin "1") (pinfunction "1_1") (pintype "bidirectional"))
      (node (ref "R32") (pin "1") (pinfunction "1_1") (pintype "passive"))
    )
    (net (code "83") (name "Net-(P10-Pad2)") (class "Default")
      (node (ref "P10") (pin "2") (pinfunction "2_2") (pintype "bidirectional"))
      (node (ref "U16") (pin "2") (pinfunction "2_2") (pintype "passive"))
    )
    (net (code "84") (name "Net-(P11-Pad1)") (class "Default")
      (node (ref "P11") (pin "1") (pinfunction "1_1") (pintype "bidirectional"))
      (node (ref "R34") (pin "1") (pinfunction "1_1") (pintype "passive"))
    )
    (net (code "85") (name "Net-(P11-Pad2)") (class "Default")
      (node (ref "P11") (pin "2") (pinfunction "2_2") (pintype "bidirectional"))
      (node (ref "U16") (pin "4") (pinfunction "4_4") (pintype "power_in"))
    )
    (net (code "86") (name "Net-(P12-Pad1)") (class "Default")
      (node (ref "P12") (pin "1") (pinfunction "1_1") (pintype "bidirectional"))
      (node (ref "R62") (pin "1") (pinfunction "1_1") (pintype "passive"))
    )
    (net (code "87") (name "Net-(P12-Pad2)") (class "Default")
      (node (ref "P12") (pin "2") (pinfunction "2_2") (pintype "bidirectional"))
      (node (ref "U16") (pin "6") (pinfunction "6_6") (pintype "power_in"))
    )
    (net (code "88") (name "Net-(P13-Pad1)") (class "Default")
      (node (ref "P13") (pin "1") (pinfunction "1_1") (pintype "bidirectional"))
      (node (ref "R64") (pin "1") (pinfunction "1_1") (pintype "passive"))
    )
    (net (code "89") (name "Net-(P13-Pad2)") (class "Default")
      (node (ref "P13") (pin "2") (pinfunction "2_2") (pintype "bidirectional"))
      (node (ref "U16") (pin "8") (pinfunction "8_8") (pintype "power_in"))
    )
    (net (code "90") (name "Net-(R9-Pad2)") (class "Default")
      (node (ref "R9") (pin "2") (pinfunction "2_2") (pintype "passive"))
      (node (ref "U2") (pin "1") (pinfunction "1_1") (pintype "passive"))
    )
    (net (code "91") (name "Net-(R10-Pad2)") (class "Default")
      (node (ref "R10") (pin "2") (pinfunction "2_2") (pintype "passive"))
      (node (ref "U2") (pin "3") (pinfunction "3_3") (pintype "passive"))
    )
    (net (code "92") (name "Net-(R16-Pad2)") (class "Default")
      (node (ref "R16") (pin "2") (pinfunction "2_2") (pintype "passive"))
      (node (ref "U2") (pin "5") (pinfunction "5_5") (pintype "power_in"))
    )
    (net (code "93") (name "Net-(R21-Pad2)") (class "Default")
      (node (ref "R21") (pin "2") (pinfunction "2_2") (pintype "passive"))
      (node (ref "U2") (pin "7") (pinfunction "7_7") (pintype "power_in"))
    )
    (net (code "94") (name "Net-(R32-Pad2)") (class "Default")
      (node (ref "R32") (pin "2") (pinfunction "2_2") (pintype "passive"))
      (node (ref "U16") (pin "1") (pinfunction "1_1") (pintype "passive"))
    )
    (net (code "95") (name "Net-(R34-Pad2)") (class "Default")
      (node (ref "R34") (pin "2") (pinfunction "2_2") (pintype "passive"))
      (node (ref "U16") (pin "3") (pinfunction "3_3") (pintype "passive"))
    )
    (net (code "96") (name "Net-(R62-Pad2)") (class "Default")
      (node (ref "R62") (pin "2") (pinfunction "2_2") (pintype "passive"))
      (node (ref "U16") (pin "5") (pinfunction "5_5") (pintype "power_in"))
    )
    (net (code "97") (name "Net-(R64-Pad2)") (class "Default")
      (node (ref "R64") (pin "2") (pinfunction "2_2") (pintype "passive"))
      (node (ref "U16") (pin "7") (pinfunction "7_7") (pintype "power_in"))
    )
    (net (code "98") (name "Net-(U1-PA9)") (class "Default")
      (node (ref "R8") (pin "2") (pinfunction "2_2") (pintype "passive"))
      (node (ref "U1") (pin "120") (pinfunction "PA9_120") (pintype "passive"))
    )
    (net (code "99") (name "Net-(U1-PC14-OSC32_IN)") (class "Default")
      (node (ref "C1") (pin "1") (pinfunction "1_1") (pintype "passive"))
      (node (ref "U1") (pin "9") (pinfunction "PC14-OSC32_IN_9") (pintype "passive"))
      (node (ref "X1") (pin "2") (pinfunction "OSC2_2") (pintype "passive"))
    )
    (net (code "100") (name "Net-(U1-PC15-OSC32_OUT)") (class "Default")
      (node (ref "C3") (pin "1") (pinfunction "1_1") (pintype "passive"))
      (node (ref "U1") (pin "10") (pinfunction "PC15-OSC32_OUT_10") (pintype "passive"))
      (node (ref "X1") (pin "1") (pinfunction "OSC1_1") (pintype "passive"))
    )
    (net (code "101") (name "Net-(U1-PDR_ON)") (class "Default")
      (node (ref "R4") (pin "2") (pinfunction "2_2") (pintype "passive"))
      (node (ref "U1") (pin "171") (pinfunction "PDR_ON_171") (pintype "passive"))
    )
    (net (code "102") (name "Net-(U1-PH0-OSC_IN)") (class "Default")
      (node (ref "C6") (pin "1") (pinfunction "1_1") (pintype "passive"))
      (node (ref "U1") (pin "29") (pinfunction "PH0-OSC_IN_29") (pintype "passive"))
      (node (ref "X2") (pin "1") (pinfunction "1_1") (pintype "passive"))
    )
    (net (code "103") (name "Net-(U1-PH1-OSC_OUT)") (class "Default")
      (node (ref "C7") (pin "1") (pinfunction "1_1") (pintype "passive"))
      (node (ref "U1") (pin "30") (pinfunction "PH1-OSC_OUT_30") (pintype "passive"))
      (node (ref "X2") (pin "3") (pinfunction "2_3") (pintype "passive"))
    )
    (net (code "104") (name "VBUS_FS1") (class "Default")
      (node (ref "R8") (pin "1") (pinfunction "1_1") (pintype "passive"))
    )
    (net (code "105") (name "VDDA") (class "Default")
      (node (ref "C10") (pin "2") (pinfunction "2_2") (pintype "passive"))
      (node (ref "C11") (pin "2") (pinfunction "2_2") (pintype "passive"))
      (node (ref "C8") (pin "2") (pinfunction "2_2") (pintype "passive"))
      (node (ref "C9") (pin "2") (pinfunction "2_2") (pintype "passive"))
      (node (ref "FB1") (pin "2") (pinfunction "2_2") (pintype "passive"))
      (node (ref "U1") (pin "38") (pinfunction "VREF+_38") (pintype "passive"))
      (node (ref "U1") (pin "39") (pinfunction "VDDA_39") (pintype "power_in"))
    )
    (net (code "106") (name "VDD_MCU") (class "Default")
      (node (ref "C14") (pin "1") (pinfunction "1_1") (pintype "passive"))
      (node (ref "C15") (pin "1") (pinfunction "1_1") (pintype "passive"))
      (node (ref "C16") (pin "1") (pinfunction "1_1") (pintype "passive"))
      (node (ref "C17") (pin "1") (pinfunction "1_1") (pintype "passive"))
      (node (ref "C18") (pin "1") (pinfunction "1_1") (pintype "passive"))
      (node (ref "C19") (pin "1") (pinfunction "1_1") (pintype "passive"))
      (node (ref "C20") (pin "1") (pinfunction "1_1") (pintype "passive"))
      (node (ref "C21") (pin "1") (pinfunction "1_1") (pintype "passive"))
      (node (ref "C22") (pin "1") (pinfunction "1_1") (pintype "passive"))
      (node (ref "C23") (pin "1") (pinfunction "1_1") (pintype "passive"))
      (node (ref "C24") (pin "1") (pinfunction "1_1") (pintype "passive"))
      (node (ref "C25") (pin "1") (pinfunction "1_1") (pintype "passive"))
      (node (ref "C26") (pin "1") (pinfunction "1_1") (pintype "passive"))
      (node (ref "C27") (pin "1") (pinfunction "1_1") (pintype "passive"))
      (node (ref "C28") (pin "1") (pinfunction "1_1") (pintype "passive"))
      (node (ref "C4") (pin "2") (pinfunction "2_2") (pintype "passive"))
      (node (ref "C5") (pin "2") (pinfunction "2_2") (pintype "passive"))
      (node (ref "FB1") (pin "1") (pinfunction "1_1") (pintype "passive"))
      (node (ref "R11") (pin "1") (pinfunction "1_1") (pintype "passive"))
      (node (ref "R25") (pin "1") (pinfunction "1_1") (pintype "passive"))
      (node (ref "R26") (pin "1") (pinfunction "1_1") (pintype "passive"))
      (node (ref "R27") (pin "1") (pinfunction "1_1") (pintype "passive"))
      (node (ref "R28") (pin "1") (pinfunction "1_1") (pintype "passive"))
      (node (ref "R31") (pin "2") (pinfunction "2_2") (pintype "passive"))
      (node (ref "R33") (pin "2") (pinfunction "2_2") (pintype "passive"))
      (node (ref "R37") (pin "2") (pinfunction "2_2") (pintype "passive"))
      (node (ref "R4") (pin "1") (pinfunction "1_1") (pintype "passive"))
      (node (ref "R40") (pin "1") (pinfunction "1_1") (pintype "passive"))
      (node (ref "R61") (pin "2") (pinfunction "2_2") (pintype "passive"))
      (node (ref "R63") (pin "2") (pinfunction "2_2") (pintype "passive"))
      (node (ref "U1") (pin "103") (pinfunction "VDD_9_103") (pintype "power_in"))
      (node (ref "U1") (pin "114") (pinfunction "VDD33_USB_114") (pintype "power_in"))
      (node (ref "U1") (pin "127") (pinfunction "VDD_10_127") (pintype "power_in"))
      (node (ref "U1") (pin "136") (pinfunction "VDD_11_136") (pintype "power_in"))
      (node (ref "U1") (pin "149") (pinfunction "VDD_12_149") (pintype "power_in"))
      (node (ref "U1") (pin "15") (pinfunction "VDD_1_15") (pintype "power_in"))
      (node (ref "U1") (pin "159") (pinfunction "VDD_13_159") (pintype "power_in"))
      (node (ref "U1") (pin "172") (pinfunction "VDD_14_172") (pintype "power_in"))
      (node (ref "U1") (pin "23") (pinfunction "VDD_2_23") (pintype "power_in"))
      (node (ref "U1") (pin "36") (pinfunction "VDD_3_36") (pintype "power_in"))
      (node (ref "U1") (pin "49") (pinfunction "VDD_4_49") (pintype "power_in"))
      (node (ref "U1") (pin "6") (pinfunction "VBAT_6") (pintype "power_in"))
      (node (ref "U1") (pin "62") (pinfunction "VDD_5_62") (pintype "power_in"))
      (node (ref "U1") (pin "72") (pinfunction "VDD_6_72") (pintype "power_in"))
      (node (ref "U1") (pin "82") (pinfunction "VDD_7_82") (pintype "power_in"))
      (node (ref "U1") (pin "91") (pinfunction "VDD_8_91") (pintype "power_in"))
    )
    (net (code "107") (name "Vin_Pr") (class "Default") (node (ref "R30") (pin "1") (pintype "passive")))
    (net (code "108") (name "unconnected-(J1-Pad7)") (class "Default")
      (node (ref "J1") (pin "7") (pinfunction "7_7") (pintype "passive+no_connect"))
    )
    (net (code "109") (name "unconnected-(U1-PA0-WKUP-Pad40)") (class "Default")
      (node (ref "U1") (pin "40") (pinfunction "PA0-WKUP_40") (pintype "passive"))
    )
    (net (code "110") (name "unconnected-(U1-PA3-Pad47)") (class "Default")
      (node (ref "U1") (pin "47") (pinfunction "PA3_47") (pintype "passive"))
    )
    (net (code "111") (name "unconnected-(U1-PA4-Pad50)") (class "Default")
      (node (ref "U1") (pin "50") (pinfunction "PA4_50") (pintype "passive"))
    )
    (net (code "112") (name "unconnected-(U1-PA5-Pad51)") (class "Default")
      (node (ref "U1") (pin "51") (pinfunction "PA5_51") (pintype "passive"))
    )
    (net (code "113") (name "unconnected-(U1-PA6-Pad52)") (class "Default")
      (node (ref "U1") (pin "52") (pinfunction "PA6_52") (pintype "passive"))
    )
    (net (code "114") (name "unconnected-(U1-PB0-Pad56)") (class "Default")
      (node (ref "U1") (pin "56") (pinfunction "PB0_56") (pintype "passive"))
    )
    (net (code "115") (name "unconnected-(U1-PB1-Pad57)") (class "Default")
      (node (ref "U1") (pin "57") (pinfunction "PB1_57") (pintype "passive"))
    )
    (net (code "116") (name "unconnected-(U1-PB2-Pad58)") (class "Default")
      (node (ref "U1") (pin "58") (pinfunction "PB2_58") (pintype "passive"))
    )
    (net (code "117") (name "unconnected-(U1-PB4-Pad162)") (class "Default")
      (node (ref "U1") (pin "162") (pinfunction "PB4_162") (pintype "passive"))
    )
    (net (code "118") (name "unconnected-(U1-PB5-Pad163)") (class "Default")
      (node (ref "U1") (pin "163") (pinfunction "PB5_163") (pintype "passive"))
    )
    (net (code "119") (name "unconnected-(U1-PB6-Pad164)") (class "Default")
      (node (ref "U1") (pin "164") (pinfunction "PB6_164") (pintype "passive"))
    )
    (net (code "120") (name "unconnected-(U1-PB7-Pad165)") (class "Default")
      (node (ref "U1") (pin "165") (pinfunction "PB7_165") (pintype "passive"))
    )
    (net (code "121") (name "unconnected-(U1-PB10-Pad79)") (class "Default")
      (node (ref "U1") (pin "79") (pinfunction "PB10_79") (pintype "passive"))
    )
    (net (code "122") (name "unconnected-(U1-PB11-Pad80)") (class "Default")
      (node (ref "U1") (pin "80") (pinfunction "PB11_80") (pintype "passive"))
    )
    (net (code "123") (name "unconnected-(U1-PC2_C-Pad34)") (class "Default")
      (node (ref "U1") (pin "34") (pinfunction "PC2_C_34") (pintype "passive"))
    )
    (net (code "124") (name "unconnected-(U1-PC3_C-Pad35)") (class "Default")
      (node (ref "U1") (pin "35") (pinfunction "PC3_C_35") (pintype "passive"))
    )
    (net (code "125") (name "unconnected-(U1-PC6-Pad115)") (class "Default")
      (node (ref "U1") (pin "115") (pinfunction "PC6_115") (pintype "passive"))
    )
    (net (code "126") (name "unconnected-(U1-PC7-Pad116)") (class "Default")
      (node (ref "U1") (pin "116") (pinfunction "PC7_116") (pintype "passive"))
    )
    (net (code "127") (name "unconnected-(U1-PC8-Pad117)") (class "Default")
      (node (ref "U1") (pin "117") (pinfunction "PC8_117") (pintype "passive"))
    )
    (net (code "128") (name "unconnected-(U1-PC9-Pad118)") (class "Default")
      (node (ref "U1") (pin "118") (pinfunction "PC9_118") (pintype "passive"))
    )
    (net (code "129") (name "unconnected-(U1-PD1-Pad143)") (class "Default")
      (node (ref "U1") (pin "143") (pinfunction "PD1_143") (pintype "passive"))
    )
    (net (code "130") (name "unconnected-(U1-PD2-Pad144)") (class "Default")
      (node (ref "U1") (pin "144") (pinfunction "PD2_144") (pintype "passive"))
    )
    (net (code "131") (name "unconnected-(U1-PD3-Pad145)") (class "Default")
      (node (ref "U1") (pin "145") (pinfunction "PD3_145") (pintype "passive"))
    )
    (net (code "132") (name "unconnected-(U1-PD4-Pad146)") (class "Default")
      (node (ref "U1") (pin "146") (pinfunction "PD4_146") (pintype "passive"))
    )
    (net (code "133") (name "unconnected-(U1-PD5-Pad147)") (class "Default")
      (node (ref "U1") (pin "147") (pinfunction "PD5_147") (pintype "passive"))
    )
    (net (code "134") (name "unconnected-(U1-PD6-Pad150)") (class "Default")
      (node (ref "U1") (pin "150") (pinfunction "PD6_150") (pintype "passive"))
    )
    (net (code "135") (name "unconnected-(U1-PD7-Pad151)") (class "Default")
      (node (ref "U1") (pin "151") (pinfunction "PD7_151") (pintype "passive"))
    )
    (net (code "136") (name "unconnected-(U1-PD8-Pad96)") (class "Default")
      (node (ref "U1") (pin "96") (pinfunction "PD8_96") (pintype "passive"))
    )
    (net (code "137") (name "unconnected-(U1-PD9-Pad97)") (class "Default")
      (node (ref "U1") (pin "97") (pinfunction "PD9_97") (pintype "passive"))
    )
    (net (code "138") (name "unconnected-(U1-PD10-Pad98)") (class "Default")
      (node (ref "U1") (pin "98") (pinfunction "PD10_98") (pintype "passive"))
    )
    (net (code "139") (name "unconnected-(U1-PD11-Pad99)") (class "Default")
      (node (ref "U1") (pin "99") (pinfunction "PD11_99") (pintype "passive"))
    )
    (net (code "140") (name "unconnected-(U1-PD12-Pad100)") (class "Default")
      (node (ref "U1") (pin "100") (pinfunction "PD12_100") (pintype "passive"))
    )
    (net (code "141") (name "unconnected-(U1-PD13-Pad101)") (class "Default")
      (node (ref "U1") (pin "101") (pinfunction "PD13_101") (pintype "passive"))
    )
    (net (code "142") (name "unconnected-(U1-PD14-Pad104)") (class "Default")
      (node (ref "U1") (pin "104") (pinfunction "PD14_104") (pintype "passive"))
    )
    (net (code "143") (name "unconnected-(U1-PD15-Pad105)") (class "Default")
      (node (ref "U1") (pin "105") (pinfunction "PD15_105") (pintype "passive"))
    )
    (net (code "144") (name "unconnected-(U1-PE0-Pad169)") (class "Default")
      (node (ref "U1") (pin "169") (pinfunction "PE0_169") (pintype "passive"))
    )
    (net (code "145") (name "unconnected-(U1-PE1-Pad170)") (class "Default")
      (node (ref "U1") (pin "170") (pinfunction "PE1_170") (pintype "passive"))
    )
    (net (code "146") (name "unconnected-(U1-PE10-Pad73)") (class "Default")
      (node (ref "U1") (pin "73") (pinfunction "PE10_73") (pintype "passive"))
    )
    (net (code "147") (name "unconnected-(U1-PE15-Pad78)") (class "Default")
      (node (ref "U1") (pin "78") (pinfunction "PE15_78") (pintype "passive"))
    )
    (net (code "148") (name "unconnected-(U1-PF0-Pad16)") (class "Default")
      (node (ref "U1") (pin "16") (pinfunction "PF0_16") (pintype "passive"))
    )
    (net (code "149") (name "unconnected-(U1-PF1-Pad17)") (class "Default")
      (node (ref "U1") (pin "17") (pinfunction "PF1_17") (pintype "passive"))
    )
    (net (code "150") (name "unconnected-(U1-PF2-Pad18)") (class "Default")
      (node (ref "U1") (pin "18") (pinfunction "PF2_18") (pintype "passive"))
    )
    (net (code "151") (name "unconnected-(U1-PF3-Pad19)") (class "Default")
      (node (ref "U1") (pin "19") (pinfunction "PF3_19") (pintype "passive"))
    )
    (net (code "152") (name "unconnected-(U1-PF6-Pad24)") (class "Default")
      (node (ref "U1") (pin "24") (pinfunction "PF6_24") (pintype "passive"))
    )
    (net (code "153") (name "unconnected-(U1-PF7-Pad25)") (class "Default")
      (node (ref "U1") (pin "25") (pinfunction "PF7_25") (pintype "passive"))
    )
    (net (code "154") (name "unconnected-(U1-PF8-Pad26)") (class "Default")
      (node (ref "U1") (pin "26") (pinfunction "PF8_26") (pintype "passive"))
    )
    (net (code "155") (name "unconnected-(U1-PF9-Pad27)") (class "Default")
      (node (ref "U1") (pin "27") (pinfunction "PF9_27") (pintype "passive"))
    )
    (net (code "156") (name "unconnected-(U1-PF10-Pad28)") (class "Default")
      (node (ref "U1") (pin "28") (pinfunction "PF10_28") (pintype "passive"))
    )
    (net (code "157") (name "unconnected-(U1-PF11-Pad59)") (class "Default")
      (node (ref "U1") (pin "59") (pinfunction "PF11_59") (pintype "passive"))
    )
    (net (code "158") (name "unconnected-(U1-PF12-Pad60)") (class "Default")
      (node (ref "U1") (pin "60") (pinfunction "PF12_60") (pintype "passive"))
    )
    (net (code "159") (name "unconnected-(U1-PF13-Pad63)") (class "Default")
      (node (ref "U1") (pin "63") (pinfunction "PF13_63") (pintype "passive"))
    )
    (net (code "160") (name "unconnected-(U1-PF14-Pad64)") (class "Default")
      (node (ref "U1") (pin "64") (pinfunction "PF14_64") (pintype "passive"))
    )
    (net (code "161") (name "unconnected-(U1-PF15-Pad65)") (class "Default")
      (node (ref "U1") (pin "65") (pinfunction "PF15_65") (pintype "passive"))
    )
    (net (code "162") (name "unconnected-(U1-PG3-Pad107)") (class "Default")
      (node (ref "U1") (pin "107") (pinfunction "PG3_107") (pintype "passive"))
    )
    (net (code "163") (name "unconnected-(U1-PG4-Pad108)") (class "Default")
      (node (ref "U1") (pin "108") (pinfunction "PG4_108") (pintype "passive"))
    )
    (net (code "164") (name "unconnected-(U1-PG5-Pad109)") (class "Default")
      (node (ref "U1") (pin "109") (pinfunction "PG5_109") (pintype "passive"))
    )
    (net (code "165") (name "unconnected-(U1-PG6-Pad110)") (class "Default")
      (node (ref "U1") (pin "110") (pinfunction "PG6_110") (pintype "passive"))
    )
    (net (code "166") (name "unconnected-(U1-PG7-Pad111)") (class "Default")
      (node (ref "U1") (pin "111") (pinfunction "PG7_111") (pintype "passive"))
    )
    (net (code "167") (name "unconnected-(U1-PG8-Pad112)") (class "Default")
      (node (ref "U1") (pin "112") (pinfunction "PG8_112") (pintype "passive"))
    )
    (net (code "168") (name "unconnected-(U1-PG9-Pad152)") (class "Default")
      (node (ref "U1") (pin "152") (pinfunction "PG9_152") (pintype "passive"))
    )
    (net (code "169") (name "unconnected-(U1-PG14-Pad157)") (class "Default")
      (node (ref "U1") (pin "157") (pinfunction "PG14_157") (pintype "passive"))
    )
    (net (code "170") (name "unconnected-(U1-PG15-Pad160)") (class "Default")
      (node (ref "U1") (pin "160") (pinfunction "PG15_160") (pintype "passive"))
    )
    (net (code "171") (name "unconnected-(U1-PH2-Pad43)") (class "Default")
      (node (ref "U1") (pin "43") (pinfunction "PH2_43") (pintype "passive"))
    )
    (net (code "172") (name "unconnected-(U1-PH3-Pad44)") (class "Default")
      (node (ref "U1") (pin "44") (pinfunction "PH3_44") (pintype "passive"))
    )
    (net (code "173") (name "unconnected-(U1-PH4-Pad45)") (class "Default")
      (node (ref "U1") (pin "45") (pinfunction "PH4_45") (pintype "passive"))
    )
    (net (code "174") (name "unconnected-(U1-PH5-Pad46)") (class "Default")
      (node (ref "U1") (pin "46") (pinfunction "PH5_46") (pintype "passive"))
    )
    (net (code "175") (name "unconnected-(U1-PH6-Pad83)") (class "Default")
      (node (ref "U1") (pin "83") (pinfunction "PH6_83") (pintype "passive"))
    )
    (net (code "176") (name "unconnected-(U1-PH15-Pad130)") (class "Default")
      (node (ref "U1") (pin "130") (pinfunction "PH15_130") (pintype "passive"))
    )
    (net (code "177") (name "unconnected-(U1-PI0-Pad131)") (class "Default")
      (node (ref "U1") (pin "131") (pinfunction "PI0_131") (pintype "passive"))
    )
    (net (code "178") (name "unconnected-(U1-PI1-Pad132)") (class "Default")
      (node (ref "U1") (pin "132") (pinfunction "PI1_132") (pintype "passive"))
    )
    (net (code "179") (name "unconnected-(U1-PI3-Pad134)") (class "Default")
      (node (ref "U1") (pin "134") (pinfunction "PI3_134") (pintype "passive"))
    )
    (net (code "180") (name "unconnected-(U1-PI4-Pad173)") (class "Default")
      (node (ref "U1") (pin "173") (pinfunction "PI4_173") (pintype "passive"))
    )
    (net (code "181") (name "unconnected-(U1-PI5-Pad174)") (class "Default")
      (node (ref "U1") (pin "174") (pinfunction "PI5_174") (pintype "passive"))
    )
    (net (code "182") (name "unconnected-(U1-PI6-Pad175)") (class "Default")
      (node (ref "U1") (pin "175") (pinfunction "PI6_175") (pintype "passive"))
    )
    (net (code "183") (name "unconnected-(U1-PI7-Pad176)") (class "Default")
      (node (ref "U1") (pin "176") (pinfunction "PI7_176") (pintype "passive"))
    )
    (net (code "184") (name "unconnected-(U1-PI9-Pad11)") (class "Default")
      (node (ref "U1") (pin "11") (pinfunction "PI9_11") (pintype "passive"))
    )
    (net (code "185") (name "unconnected-(U1-PI10-Pad12)") (class "Default")
      (node (ref "U1") (pin "12") (pinfunction "PI10_12") (pintype "passive"))
    )
  )
)
